# v_reg_based_CC_circuit.net
KiCad netlist of a schematic drawn in EAGLE
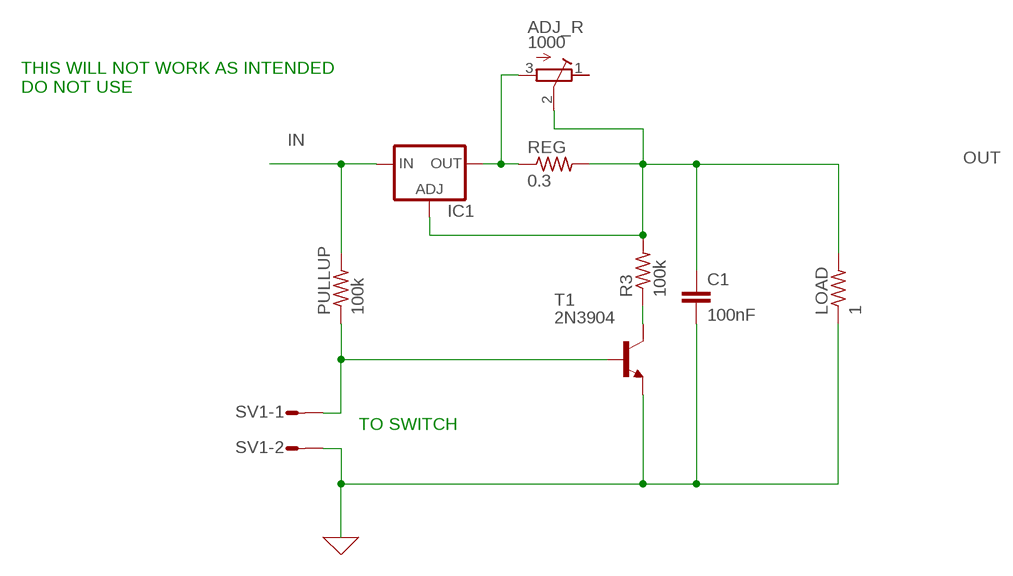
[diagram p0: schematic, sheet 1]

(export (version "E")
  (design (tool "Eeschema 10.0.6"))
  (components
    (comp (ref "ADJ_R")
      (value "1000")
      (footprint "eagle-import:RTRIMT93XA")
      (libsource (lib "eagle-import") (part "R-TRIMMT93XA"))
    )
    (comp (ref "C1")
      (value "100nF")
      (footprint "eagle-import:C2.5-2")
      (libsource (lib "eagle-import") (part "C2.5/2"))
    )
    (comp (ref "IC1")
      (value "LM317TS")
      (footprint "eagle-import:317TS")
      (libsource (lib "eagle-import") (part "LM317TS"))
    )
    (comp (ref "LOAD")
      (value "1")
      (footprint "eagle-import:0617V")
      (libsource (lib "eagle-import") (part "R-US_0617/5V"))
    )
    (comp (ref "PULLUP")
      (value "100k")
      (footprint "eagle-import:0207_7")
      (libsource (lib "eagle-import") (part "R-US_0207/7"))
    )
    (comp (ref "R3")
      (value "100k")
      (footprint "eagle-import:0207_7")
      (libsource (lib "eagle-import") (part "R-US_0207/7"))
    )
    (comp (ref "REG")
      (value "0.3")
      (footprint "eagle-import:P0817V")
      (libsource (lib "eagle-import") (part "R-US_0817/7V"))
    )
    (comp (ref "SV1")
      (value "L02P")
      (footprint "eagle-import:L02P")
      (libsource (lib "eagle-import") (part "L02P"))
    )
    (comp (ref "T1")
      (value "2N3904")
      (footprint "eagle-import:TO92")
      (libsource (lib "eagle-import") (part "2N3904"))
    )
  )
  (nets
    (net (code "1") (name "/IN") (class "Default")
      (node (ref "IC1") (pin "3") (pinfunction "IN_3") (pintype "input"))
      (node (ref "PULLUP") (pin "2") (pinfunction "2_2") (pintype "passive"))
    )
    (net (code "2") (name "/OUT") (class "Default")
      (node (ref "ADJ_R") (pin "2") (pinfunction "S_2") (pintype "passive"))
      (node (ref "C1") (pin "1") (pinfunction "1_1") (pintype "passive"))
      (node (ref "IC1") (pin "1") (pinfunction "ADJ_1") (pintype "input"))
      (node (ref "LOAD") (pin "2") (pinfunction "2_2") (pintype "passive"))
      (node (ref "R3") (pin "2") (pinfunction "2_2") (pintype "passive"))
      (node (ref "REG") (pin "2") (pinfunction "2_2") (pintype "passive"))
    )
    (net (code "3") (name "GND") (class "Default")
      (node (ref "C1") (pin "2") (pinfunction "2_2") (pintype "passive"))
      (node (ref "LOAD") (pin "1") (pinfunction "1_1") (pintype "passive"))
      (node (ref "SV1") (pin "2") (pinfunction "S_2") (pintype "passive"))
      (node (ref "T1") (pin "3") (pinfunction "E_3") (pintype "passive"))
    )
    (net (code "4") (name "Net-(ADJ_R-A)") (class "Default")
      (node (ref "ADJ_R") (pin "3") (pinfunction "A_3") (pintype "passive"))
      (node (ref "IC1") (pin "2") (pinfunction "OUT_2") (pintype "passive"))
      (node (ref "REG") (pin "1") (pinfunction "1_1") (pintype "passive"))
    )
    (net (code "5") (name "Net-(SV1A-S)") (class "Default")
      (node (ref "PULLUP") (pin "1") (pinfunction "1_1") (pintype "passive"))
      (node (ref "SV1") (pin "1") (pinfunction "S_1") (pintype "passive"))
      (node (ref "T1") (pin "2") (pinfunction "B_2") (pintype "passive"))
    )
    (net (code "6") (name "Net-(T1-C)") (class "Default")
      (node (ref "R3") (pin "1") (pinfunction "1_1") (pintype "passive"))
      (node (ref "T1") (pin "1") (pinfunction "C_1") (pintype "passive"))
    )
    (net (code "7") (name "unconnected-(ADJ_R-E-Pad1)") (class "Default")
      (node (ref "ADJ_R") (pin "1") (pinfunction "E_1") (pintype "passive"))
    )
  )
)
